# MCU.net
KiCad netlist of a schematic drawn in Altium Designer
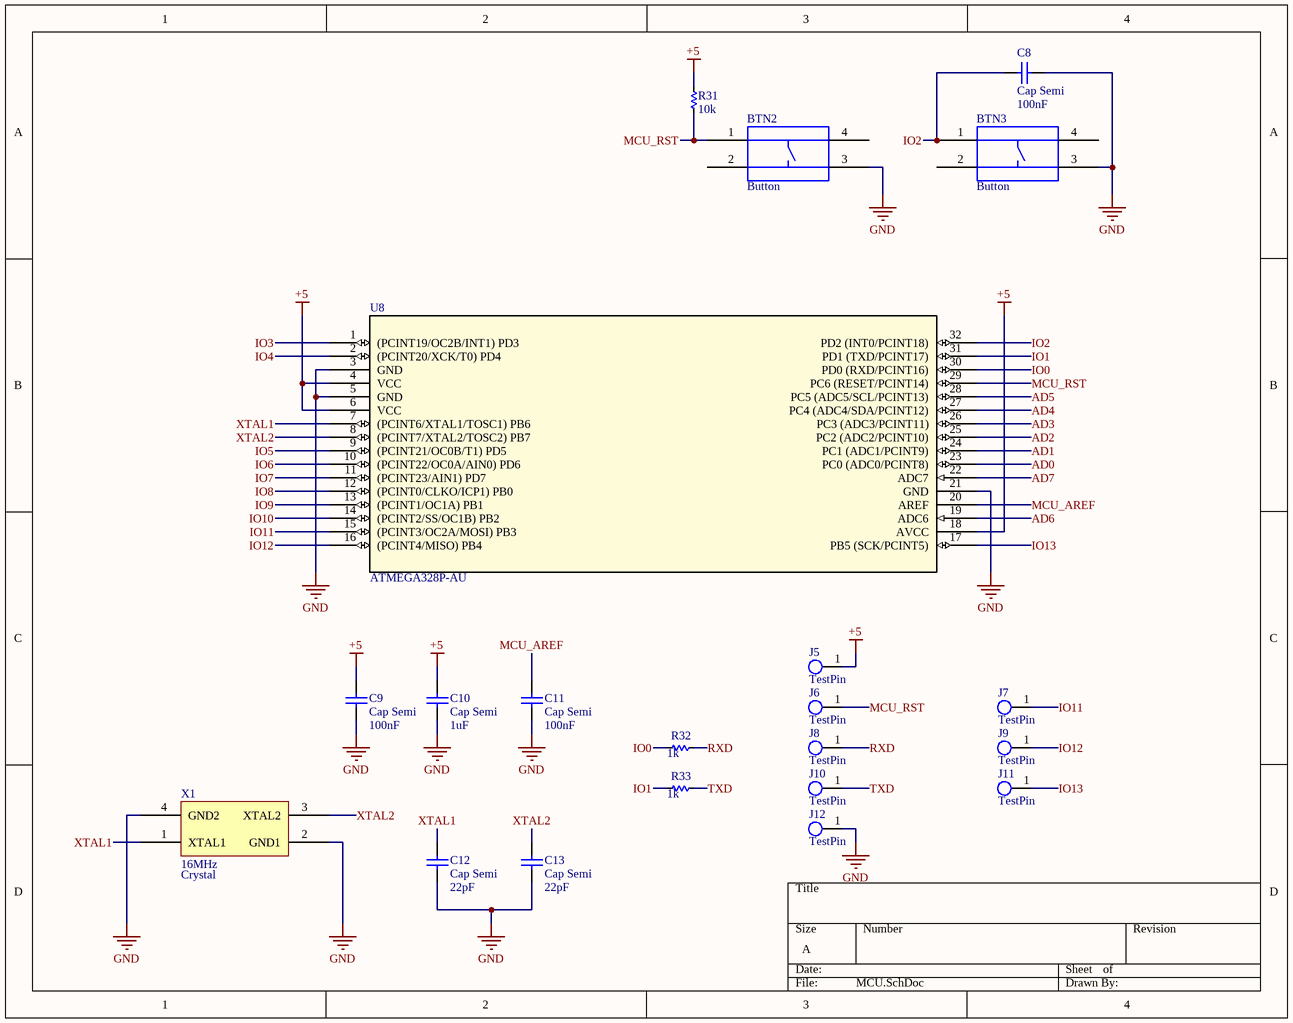
[diagram p0: MCU.SchDoc]

(export (version "E")
  (design (tool "Eeschema 10.0.6"))
  (components
    (comp (ref "BTN2")
      (value "Button")
      (footprint "TactileButton_4x4")
      (libsource (lib "TactileButton_4x4") (part "Tactile_4x4"))
    )
    (comp (ref "BTN3")
      (value "Button")
      (footprint "TactileButton_4x4")
      (libsource (lib "TactileButton_4x4") (part "Tactile_4x4"))
    )
    (comp (ref "C8")
      (value "Cap Semi")
      (footprint "1608[0603]")
      (description "Capacitor (Semiconductor SIM Model)")
      (fields (field (name "ALTIUM_VALUE") "100nF") (field (name "PUBLISHER") "Altium Limited"))
      (libsource (lib "Miscellaneous Devices") (part "Cap Semi"))
    )
    (comp (ref "C9")
      (value "Cap Semi")
      (footprint "1608[0603]")
      (description "Capacitor (Semiconductor SIM Model)")
      (fields (field (name "ALTIUM_VALUE") "100nF") (field (name "PUBLISHER") "Altium Limited"))
      (libsource (lib "Miscellaneous Devices") (part "Cap Semi"))
    )
    (comp (ref "C10")
      (value "Cap Semi")
      (footprint "1608[0603]")
      (description "Capacitor (Semiconductor SIM Model)")
      (fields (field (name "ALTIUM_VALUE") "1uF") (field (name "PUBLISHER") "Altium Limited"))
      (libsource (lib "Miscellaneous Devices") (part "Cap Semi"))
    )
    (comp (ref "C11")
      (value "Cap Semi")
      (footprint "1608[0603]")
      (description "Capacitor (Semiconductor SIM Model)")
      (fields (field (name "ALTIUM_VALUE") "100nF") (field (name "PUBLISHER") "Altium Limited"))
      (libsource (lib "Miscellaneous Devices") (part "Cap Semi"))
    )
    (comp (ref "C12")
      (value "Cap Semi")
      (footprint "1608[0603]")
      (description "Capacitor (Semiconductor SIM Model)")
      (fields (field (name "ALTIUM_VALUE") "22pF") (field (name "PUBLISHER") "Altium Limited"))
      (libsource (lib "Miscellaneous Devices") (part "Cap Semi"))
    )
    (comp (ref "C13")
      (value "Cap Semi")
      (footprint "1608[0603]")
      (description "Capacitor (Semiconductor SIM Model)")
      (fields (field (name "ALTIUM_VALUE") "22pF") (field (name "PUBLISHER") "Altium Limited"))
      (libsource (lib "Miscellaneous Devices") (part "Cap Semi"))
    )
    (comp (ref "J5")
      (value "TestPin")
      (footprint "TestPin_1mm")
      (description "Test conntact for pogo pins")
      (libsource (lib "TestPin") (part "TestPin_1mm"))
    )
    (comp (ref "J6")
      (value "TestPin")
      (footprint "TestPin_1mm")
      (description "Test conntact for pogo pins")
      (libsource (lib "TestPin") (part "TestPin_1mm"))
    )
    (comp (ref "J7")
      (value "TestPin")
      (footprint "TestPin_1mm")
      (description "Test conntact for pogo pins")
      (libsource (lib "TestPin") (part "TestPin_1mm"))
    )
    (comp (ref "J8")
      (value "TestPin")
      (footprint "TestPin_1mm")
      (description "Test conntact for pogo pins")
      (libsource (lib "TestPin") (part "TestPin_1mm"))
    )
    (comp (ref "J9")
      (value "TestPin")
      (footprint "TestPin_1mm")
      (description "Test conntact for pogo pins")
      (libsource (lib "TestPin") (part "TestPin_1mm"))
    )
    (comp (ref "J10")
      (value "TestPin")
      (footprint "TestPin_1mm")
      (description "Test conntact for pogo pins")
      (libsource (lib "TestPin") (part "TestPin_1mm"))
    )
    (comp (ref "J11")
      (value "TestPin")
      (footprint "TestPin_1mm")
      (description "Test conntact for pogo pins")
      (libsource (lib "TestPin") (part "TestPin_1mm"))
    )
    (comp (ref "J12")
      (value "TestPin")
      (footprint "TestPin_1mm")
      (description "Test conntact for pogo pins")
      (libsource (lib "TestPin") (part "TestPin_1mm"))
    )
    (comp (ref "R31")
      (value "10k")
      (footprint "RES-SMD-0603")
      (description "Resistor")
      (fields
        (field (name "MANUFACTURER") "Generic Components")
        (field (name "Comment") "Res")
        (field (name "PUBLISHER") "Altium Hobart Technology Centre")
      )
      (libsource (lib "LIBRARY") (part "Res-SMD"))
    )
    (comp (ref "R32")
      (value "1k")
      (footprint "RES-SMD-0603")
      (description "Resistor")
      (fields
        (field (name "MANUFACTURER") "Generic Components")
        (field (name "Comment") "Res")
        (field (name "PUBLISHER") "Altium Hobart Technology Centre")
      )
      (libsource (lib "LIBRARY") (part "Res-SMD"))
    )
    (comp (ref "R33")
      (value "1k")
      (footprint "RES-SMD-0603")
      (description "Resistor")
      (fields
        (field (name "MANUFACTURER") "Generic Components")
        (field (name "Comment") "Res")
        (field (name "PUBLISHER") "Altium Hobart Technology Centre")
      )
      (libsource (lib "LIBRARY") (part "Res-SMD"))
    )
    (comp (ref "U8")
      (value "ATMEGA328P-AU")
      (footprint "32A_ATM")
      (description "No Description Available")
      (fields (field (name "COPYRIGHT") "Copyright (C) 2018 Accelerated Designs. All rights reserved"))
      (libsource (lib "ATMega328P-AU") (part "ATMEGA328P-AU"))
    )
    (comp (ref "X1")
      (value "Crystal")
      (footprint "SMD-3225-4P")
      (description "16MHz ±25ppm SMD3225-4P Oscillators ROHS")
      (libsource (lib "Crystal-3225") (part "Crystal 3225"))
    )
  )
  (nets
    (net (code "1") (name "+5") (class "Default")
      (node (ref "C10") (pin "2") (pinfunction "2_2") (pintype "passive"))
      (node (ref "C9") (pin "2") (pinfunction "2_2") (pintype "passive"))
      (node (ref "J5") (pin "1") (pinfunction "1_1") (pintype "passive"))
      (node (ref "R31") (pin "1") (pinfunction "1_1") (pintype "passive"))
      (node (ref "U8") (pin "18") (pinfunction "AVCC_18") (pintype "power_in"))
      (node (ref "U8") (pin "4") (pinfunction "VCC_4") (pintype "power_in"))
      (node (ref "U8") (pin "6") (pinfunction "VCC_6") (pintype "power_in"))
    )
    (net (code "2") (name "/AD0") (class "Default")
      (node (ref "U8") (pin "23") (pinfunction "PC0_(ADC0/PCINT8)_23") (pintype "bidirectional"))
    )
    (net (code "3") (name "/AD1") (class "Default")
      (node (ref "U8") (pin "24") (pinfunction "PC1_(ADC1/PCINT9)_24") (pintype "bidirectional"))
    )
    (net (code "4") (name "/AD2") (class "Default")
      (node (ref "U8") (pin "25") (pinfunction "PC2_(ADC2/PCINT10)_25") (pintype "bidirectional"))
    )
    (net (code "5") (name "/AD3") (class "Default")
      (node (ref "U8") (pin "26") (pinfunction "PC3_(ADC3/PCINT11)_26") (pintype "bidirectional"))
    )
    (net (code "6") (name "/AD4") (class "Default")
      (node (ref "U8") (pin "27") (pinfunction "PC4_(ADC4/SDA/PCINT12)_27") (pintype "bidirectional"))
    )
    (net (code "7") (name "/AD5") (class "Default")
      (node (ref "U8") (pin "28") (pinfunction "PC5_(ADC5/SCL/PCINT13)_28") (pintype "bidirectional"))
    )
    (net (code "8") (name "/AD6") (class "Default")
      (node (ref "U8") (pin "19") (pinfunction "ADC6_19") (pintype "input"))
    )
    (net (code "9") (name "/AD7") (class "Default")
      (node (ref "U8") (pin "22") (pinfunction "ADC7_22") (pintype "input"))
    )
    (net (code "10") (name "/IO0") (class "Default")
      (node (ref "R32") (pin "2") (pinfunction "2_2") (pintype "passive"))
      (node (ref "U8") (pin "30") (pinfunction "PD0_(RXD/PCINT16)_30") (pintype "bidirectional"))
    )
    (net (code "11") (name "/IO1") (class "Default")
      (node (ref "R33") (pin "2") (pinfunction "2_2") (pintype "passive"))
      (node (ref "U8") (pin "31") (pinfunction "PD1_(TXD/PCINT17)_31") (pintype "bidirectional"))
    )
    (net (code "12") (name "/IO2") (class "Default")
      (node (ref "BTN3") (pin "1") (pinfunction "Pin1_1") (pintype "passive"))
      (node (ref "C8") (pin "2") (pinfunction "2_2") (pintype "passive"))
      (node (ref "U8") (pin "32") (pinfunction "PD2_(INT0/PCINT18)_32") (pintype "bidirectional"))
    )
    (net (code "13") (name "/IO3") (class "Default")
      (node (ref "U8") (pin "1") (pinfunction "(PCINT19/OC2B/INT1)_PD3_1") (pintype "bidirectional"))
    )
    (net (code "14") (name "/IO4") (class "Default")
      (node (ref "U8") (pin "2") (pinfunction "(PCINT20/XCK/T0)_PD4_2") (pintype "bidirectional"))
    )
    (net (code "15") (name "/IO5") (class "Default")
      (node (ref "U8") (pin "9") (pinfunction "(PCINT21/OC0B/T1)_PD5_9") (pintype "bidirectional"))
    )
    (net (code "16") (name "/IO6") (class "Default")
      (node (ref "U8") (pin "10") (pinfunction "(PCINT22/OC0A/AIN0)_PD6_10") (pintype "bidirectional"))
    )
    (net (code "17") (name "/IO7") (class "Default")
      (node (ref "U8") (pin "11") (pinfunction "(PCINT23/AIN1)_PD7_11") (pintype "bidirectional"))
    )
    (net (code "18") (name "/IO8") (class "Default")
      (node (ref "U8") (pin "12") (pinfunction "(PCINT0/CLKO/ICP1)_PB0_12") (pintype "bidirectional"))
    )
    (net (code "19") (name "/IO9") (class "Default")
      (node (ref "U8") (pin "13") (pinfunction "(PCINT1/OC1A)_PB1_13") (pintype "bidirectional"))
    )
    (net (code "20") (name "/IO10") (class "Default")
      (node (ref "U8") (pin "14") (pinfunction "(PCINT2/SS/OC1B)_PB2_14") (pintype "bidirectional"))
    )
    (net (code "21") (name "/IO11") (class "Default")
      (node (ref "J7") (pin "1") (pinfunction "1_1") (pintype "passive"))
      (node (ref "U8") (pin "15") (pinfunction "(PCINT3/OC2A/MOSI)_PB3_15") (pintype "bidirectional"))
    )
    (net (code "22") (name "/IO12") (class "Default")
      (node (ref "J9") (pin "1") (pinfunction "1_1") (pintype "passive"))
      (node (ref "U8") (pin "16") (pinfunction "(PCINT4/MISO)_PB4_16") (pintype "bidirectional"))
    )
    (net (code "23") (name "/IO13") (class "Default")
      (node (ref "J11") (pin "1") (pinfunction "1_1") (pintype "passive"))
      (node (ref "U8") (pin "17") (pinfunction "PB5_(SCK/PCINT5)_17") (pintype "bidirectional"))
    )
    (net (code "24") (name "/MCU_AREF") (class "Default")
      (node (ref "C11") (pin "2") (pinfunction "2_2") (pintype "passive"))
      (node (ref "U8") (pin "20") (pinfunction "AREF_20") (pintype "passive"))
    )
    (net (code "25") (name "/MCU_RST") (class "Default")
      (node (ref "BTN2") (pin "1") (pinfunction "Pin1_1") (pintype "passive"))
      (node (ref "J6") (pin "1") (pinfunction "1_1") (pintype "passive"))
      (node (ref "R31") (pin "2") (pinfunction "2_2") (pintype "passive"))
      (node (ref "U8") (pin "29") (pinfunction "PC6_(RESET/PCINT14)_29") (pintype "bidirectional"))
    )
    (net (code "26") (name "/RXD") (class "Default")
      (node (ref "J8") (pin "1") (pinfunction "1_1") (pintype "passive"))
      (node (ref "R32") (pin "1") (pinfunction "1_1") (pintype "passive"))
    )
    (net (code "27") (name "/TXD") (class "Default")
      (node (ref "J10") (pin "1") (pinfunction "1_1") (pintype "passive"))
      (node (ref "R33") (pin "1") (pinfunction "1_1") (pintype "passive"))
    )
    (net (code "28") (name "/XTAL1") (class "Default")
      (node (ref "C12") (pin "2") (pinfunction "2_2") (pintype "passive"))
      (node (ref "U8") (pin "7") (pinfunction "(PCINT6/XTAL1/TOSC1)_PB6_7") (pintype "bidirectional"))
      (node (ref "X1") (pin "1") (pinfunction "XTAL1_1") (pintype "passive"))
    )
    (net (code "29") (name "/XTAL2") (class "Default")
      (node (ref "C13") (pin "2") (pinfunction "2_2") (pintype "passive"))
      (node (ref "U8") (pin "8") (pinfunction "(PCINT7/XTAL2/TOSC2)_PB7_8") (pintype "bidirectional"))
      (node (ref "X1") (pin "3") (pinfunction "XTAL2_3") (pintype "passive"))
    )
    (net (code "30") (name "GND") (class "Default")
      (node (ref "BTN2") (pin "3") (pinfunction "Pin3_3") (pintype "passive"))
      (node (ref "BTN3") (pin "3") (pinfunction "Pin3_3") (pintype "passive"))
      (node (ref "C10") (pin "1") (pinfunction "1_1") (pintype "passive"))
      (node (ref "C11") (pin "1") (pinfunction "1_1") (pintype "passive"))
      (node (ref "C12") (pin "1") (pinfunction "1_1") (pintype "passive"))
      (node (ref "C13") (pin "1") (pinfunction "1_1") (pintype "passive"))
      (node (ref "C8") (pin "1") (pinfunction "1_1") (pintype "passive"))
      (node (ref "C9") (pin "1") (pinfunction "1_1") (pintype "passive"))
      (node (ref "J12") (pin "1") (pinfunction "1_1") (pintype "passive"))
      (node (ref "U8") (pin "21") (pinfunction "GND_21") (pintype "power_in"))
      (node (ref "U8") (pin "3") (pinfunction "GND_3") (pintype "power_in"))
      (node (ref "U8") (pin "5") (pinfunction "GND_5") (pintype "power_in"))
      (node (ref "X1") (pin "2") (pinfunction "GND1_2") (pintype "passive"))
      (node (ref "X1") (pin "4") (pinfunction "GND2_4") (pintype "passive"))
    )
    (net (code "31") (name "unconnected-(BTN2-Pin2-Pad2)") (class "Default")
      (node (ref "BTN2") (pin "2") (pinfunction "Pin2_2") (pintype "passive"))
    )
    (net (code "32") (name "unconnected-(BTN2-Pin4-Pad4)") (class "Default")
      (node (ref "BTN2") (pin "4") (pinfunction "Pin4_4") (pintype "passive"))
    )
    (net (code "33") (name "unconnected-(BTN3-Pin2-Pad2)") (class "Default")
      (node (ref "BTN3") (pin "2") (pinfunction "Pin2_2") (pintype "passive"))
    )
    (net (code "34") (name "unconnected-(BTN3-Pin4-Pad4)") (class "Default")
      (node (ref "BTN3") (pin "4") (pinfunction "Pin4_4") (pintype "passive"))
    )
  )
)
